# Schematic.net
KiCad netlist of a schematic drawn in Altium Designer
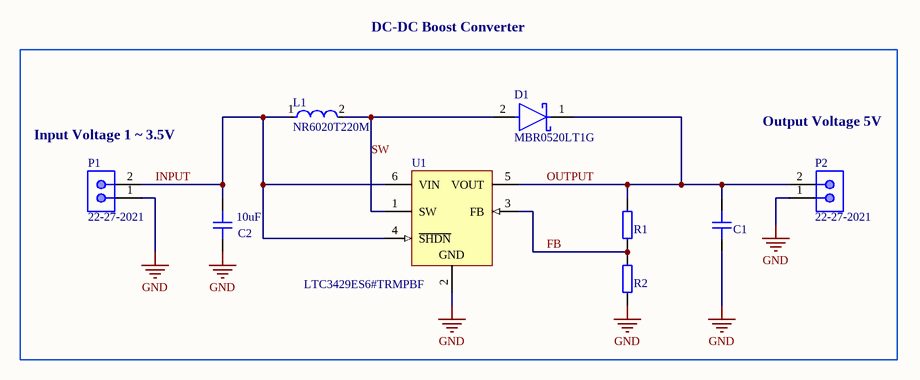
[diagram p0: Schematic.SchDoc]

(export (version "E")
  (design (tool "Eeschema 10.0.6"))
  (components
    (comp (ref "C1")
      (value "CAP_0603")
      (footprint "CAP_0603")
      (description "Capacitor SMD 0603")
      (fields (field (name "SOURCE") "Schematic-Lib-PhilsLab.SchLib"))
      (libsource (lib "Industrial University of Ho Chi Minh City") (part "CAP_EL_NP_5MM"))
    )
    (comp (ref "C2")
      (value "10uF")
      (footprint "CAP_0603")
      (description "Capacitor SMD 0603")
      (fields (field (name "SOURCE") "Schematic-Lib-PhilsLab.SchLib"))
      (libsource (lib "Industrial University of Ho Chi Minh City") (part "CAP_EL_NP_5MM"))
    )
    (comp (ref "D1")
      (value "MBR0520LT1G")
      (footprint "FP-425-04-IPC_C")
      (description "DIODE SCHOTTKY 20V 500MA SOD123")
      (libsource (lib "Altium Content Vault") (part "1d6ec82d83fb6aee721767c19dac4b9"))
    )
    (comp (ref "L1")
      (value "NR6020T220M")
      (footprint "FP-NR6020-MFG")
      (description "SMD Power Inductors 22uH ±20% 0.95A 0.348Ω")
      (fields (field (name "TOLERANCE") "20%"))
      (libsource (lib "Altium Content Vault") (part "725321dda6339637d4d059423bc1c3c"))
    )
    (comp (ref "P1")
      (value "22-27-2021")
      (footprint "MOLX-22-27-2021_V")
      (fields (field (name "MANUFACTURER") "Molex") (field (name "PARTNUMBER") "0022272021"))
      (libsource (lib "Altium Content Vault") (part "CN-1P-M-R2"))
    )
    (comp (ref "P2")
      (value "22-27-2021")
      (footprint "MOLX-22-27-2021_V")
      (fields (field (name "MANUFACTURER") "Molex") (field (name "PARTNUMBER") "0022272021"))
      (libsource (lib "") (part "CN-1P-M-R2_1"))
    )
    (comp (ref "R1")
      (value "RES_0603")
      (footprint "RES_0603")
      (description "Resistor SMD 0603")
      (fields (field (name "SOURCE") "Schematic-Lib-PhilsLab.SchLib"))
      (libsource (lib "Industrial University of Ho Chi Minh City") (part "RES_5931"))
    )
    (comp (ref "R2")
      (value "RES_0603")
      (footprint "RES_0603")
      (description "Resistor SMD 0603")
      (fields (field (name "SOURCE") "Schematic-Lib-PhilsLab.SchLib"))
      (libsource (lib "Industrial University of Ho Chi Minh City") (part "RES_5931"))
    )
    (comp (ref "U1")
      (value "LTC3429ES6#TRMPBF")
      (footprint "LT-S6-6-TSOT-23_L")
      (fields (field (name "MANUFACTURER") "Linear Technology"))
      (libsource (lib "Altium Content Vault") (part "LT-LTC34XXX_LT34XXX"))
    )
  )
  (nets
    (net (code "1") (name "/FB") (class "Default")
      (node (ref "R1") (pin "1") (pinfunction "1_1") (pintype "passive"))
      (node (ref "R2") (pin "1") (pinfunction "1_1") (pintype "passive"))
      (node (ref "U1") (pin "3") (pinfunction "FB_3") (pintype "input"))
    )
    (net (code "2") (name "/INPUT") (class "Default")
      (node (ref "C2") (pin "2") (pinfunction "2_2") (pintype "passive"))
      (node (ref "L1") (pin "1") (pinfunction "1_1") (pintype "passive"))
      (node (ref "P1") (pin "2") (pinfunction "2_2") (pintype "passive"))
      (node (ref "U1") (pin "4") (pinfunction "~{SHDN}_4") (pintype "input"))
      (node (ref "U1") (pin "6") (pinfunction "VIN_6") (pintype "power_in"))
    )
    (net (code "3") (name "/OUTPUT") (class "Default")
      (node (ref "C1") (pin "2") (pinfunction "2_2") (pintype "passive"))
      (node (ref "D1") (pin "1") (pinfunction "C_1") (pintype "passive"))
      (node (ref "P2") (pin "2") (pinfunction "2_2") (pintype "passive"))
      (node (ref "R1") (pin "2") (pinfunction "2_2") (pintype "passive"))
      (node (ref "U1") (pin "5") (pinfunction "VOUT_5") (pintype "power_in"))
    )
    (net (code "4") (name "/SW") (class "Default")
      (node (ref "D1") (pin "2") (pinfunction "A_2") (pintype "passive"))
      (node (ref "L1") (pin "2") (pinfunction "2_2") (pintype "passive"))
      (node (ref "U1") (pin "1") (pinfunction "SW_1") (pintype "passive"))
    )
    (net (code "5") (name "GND") (class "Default")
      (node (ref "C1") (pin "1") (pinfunction "1_1") (pintype "passive"))
      (node (ref "C2") (pin "1") (pinfunction "1_1") (pintype "passive"))
      (node (ref "P1") (pin "1") (pinfunction "1_1") (pintype "passive"))
      (node (ref "P2") (pin "1") (pinfunction "1_1") (pintype "passive"))
      (node (ref "R2") (pin "2") (pinfunction "2_2") (pintype "passive"))
      (node (ref "U1") (pin "2") (pinfunction "GND_2") (pintype "power_in"))
    )
  )
)
